# Atmega32AU-Basic.net
KiCad netlist of a schematic drawn in EAGLE
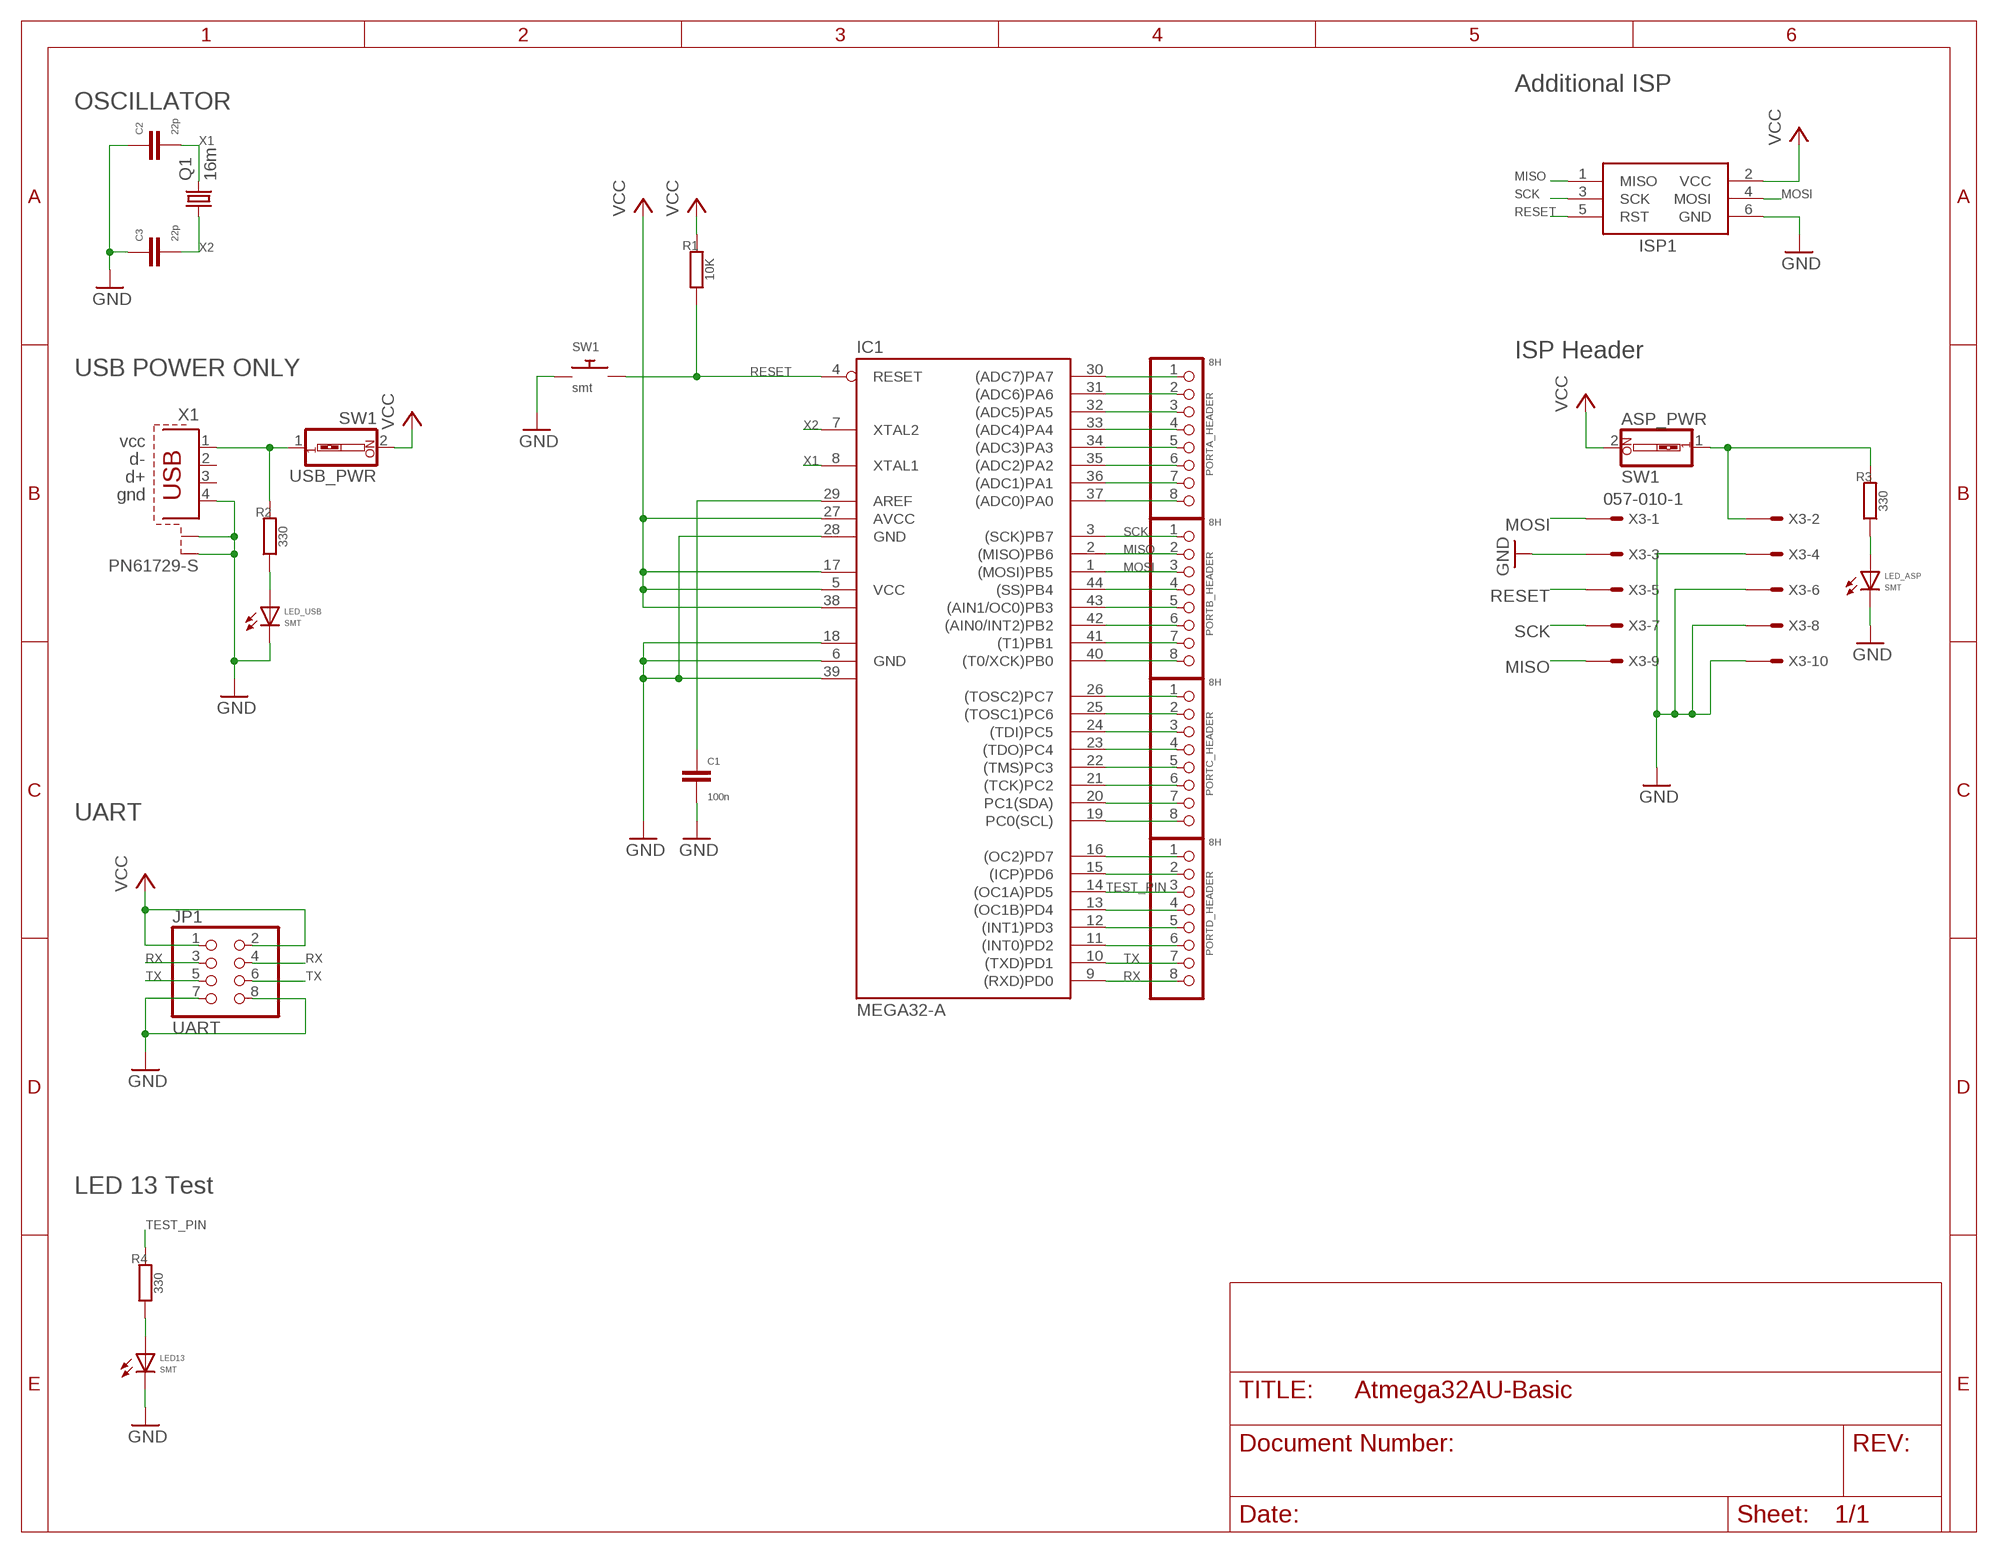
[diagram p0: schematic, sheet 1]

(export (version "E")
  (design (tool "Eeschema 10.0.6"))
  (components
    (comp (ref "ASP_PWR")
      (value "SW1")
      (footprint "eagle-import:EDG-01")
      (libsource (lib "eagle-import") (part "SW_DIP-1"))
    )
    (comp (ref "C1")
      (value "100n")
      (footprint "eagle-import:C1206")
      (libsource (lib "eagle-import") (part "C-EUC1206"))
    )
    (comp (ref "C2")
      (value "22p")
      (footprint "eagle-import:C1206")
      (libsource (lib "eagle-import") (part "C-EUC1206"))
    )
    (comp (ref "C3")
      (value "22p")
      (footprint "eagle-import:C1206")
      (libsource (lib "eagle-import") (part "C-EUC1206"))
    )
    (comp (ref "IC1")
      (value "MEGA32-A")
      (footprint "eagle-import:TQFP44")
      (fields (field (name "MPN") "ATMEGA32-16AU"))
      (libsource (lib "eagle-import") (part "MEGA32-A"))
    )
    (comp (ref "ISP1")
      (value "AVRISP-6")
      (footprint "eagle-import:AVRISP")
      (libsource (lib "eagle-import") (part "AVRISP-6"))
    )
    (comp (ref "JP1")
      (value "UART")
      (footprint "eagle-import:2X04")
      (libsource (lib "eagle-import") (part "PINHD-2X4"))
    )
    (comp (ref "LED13")
      (value "SMT")
      (footprint "eagle-import:1206")
      (libsource (lib "eagle-import") (part "LEDSMT1206"))
    )
    (comp (ref "LED_ASP")
      (value "SMT")
      (footprint "eagle-import:1206")
      (libsource (lib "eagle-import") (part "LEDSMT1206"))
    )
    (comp (ref "LED_USB")
      (value "SMT")
      (footprint "eagle-import:1206")
      (libsource (lib "eagle-import") (part "LEDSMT1206"))
    )
    (comp (ref "PORTA_HEADER")
      (value "8H")
      (footprint "eagle-import:1X08-BIG")
      (libsource (lib "eagle-import") (part "PINHD-1X8BIG"))
    )
    (comp (ref "PORTB_HEADER")
      (value "8H")
      (footprint "eagle-import:1X08-BIG")
      (libsource (lib "eagle-import") (part "PINHD-1X8BIG"))
    )
    (comp (ref "PORTC_HEADER")
      (value "8H")
      (footprint "eagle-import:1X08-BIG")
      (libsource (lib "eagle-import") (part "PINHD-1X8BIG"))
    )
    (comp (ref "PORTD_HEADER")
      (value "8H")
      (footprint "eagle-import:1X08-BIG")
      (libsource (lib "eagle-import") (part "PINHD-1X8BIG"))
    )
    (comp (ref "Q1")
      (value "16m")
      (footprint "eagle-import:HC49UP")
      (libsource (lib "eagle-import") (part "CRYSTALHC49UP"))
    )
    (comp (ref "R1")
      (value "10K")
      (footprint "eagle-import:M1206")
      (libsource (lib "eagle-import") (part "R-EU_M1206"))
    )
    (comp (ref "R2")
      (value "330")
      (footprint "eagle-import:M1206")
      (libsource (lib "eagle-import") (part "R-EU_M1206"))
    )
    (comp (ref "R3")
      (value "330")
      (footprint "eagle-import:M1206")
      (libsource (lib "eagle-import") (part "R-EU_M1206"))
    )
    (comp (ref "R4")
      (value "330")
      (footprint "eagle-import:M1206")
      (libsource (lib "eagle-import") (part "R-EU_M1206"))
    )
    (comp (ref "SW1")
      (value "smt")
      (footprint "eagle-import:TACT_PANA-EVQ")
      (libsource (lib "eagle-import") (part "SWITCH_PUSHBUTTONEVQ-PE"))
    )
    (comp (ref "USB_PWR")
      (value "SW1")
      (footprint "eagle-import:EDG-01")
      (libsource (lib "eagle-import") (part "SW_DIP-1"))
    )
    (comp (ref "X1")
      (value "PN61729-S")
      (footprint "eagle-import:PN61729-S")
      (libsource (lib "eagle-import") (part "PN61729-S"))
    )
    (comp (ref "X3")
      (value "057-010-1")
      (footprint "eagle-import:057-010-1")
      (libsource (lib "eagle-import") (part "057-010-1"))
    )
  )
  (nets
    (net (code "1") (name "/MISO") (class "Default")
      (node (ref "IC1") (pin "2") (pinfunction "(MISO)PB6_2") (pintype "bidirectional"))
      (node (ref "ISP1") (pin "1") (pinfunction "MISO_1") (pintype "input"))
      (node (ref "PORTB_HEADER") (pin "2") (pinfunction "2_2") (pintype "passive"))
      (node (ref "X3") (pin "9") (pinfunction "S_9") (pintype "passive"))
    )
    (net (code "2") (name "/MOSI") (class "Default")
      (node (ref "IC1") (pin "1") (pinfunction "(MOSI)PB5_1") (pintype "bidirectional"))
      (node (ref "ISP1") (pin "4") (pinfunction "MOSI_4") (pintype "output"))
      (node (ref "PORTB_HEADER") (pin "3") (pinfunction "3_3") (pintype "passive"))
      (node (ref "X3") (pin "1") (pinfunction "S_1") (pintype "passive"))
    )
    (net (code "3") (name "/RESET") (class "Default")
      (node (ref "IC1") (pin "4") (pinfunction "RESET_4") (pintype "input"))
      (node (ref "ISP1") (pin "5") (pinfunction "RST_5") (pintype "output"))
      (node (ref "R1") (pin "1") (pinfunction "1_1") (pintype "passive"))
      (node (ref "SW1") (pin "P$2") (pinfunction "P$2_P$2") (pintype "passive"))
      (node (ref "X3") (pin "5") (pinfunction "S_5") (pintype "passive"))
    )
    (net (code "4") (name "/RX") (class "Default")
      (node (ref "IC1") (pin "9") (pinfunction "(RXD)PD0_9") (pintype "bidirectional"))
      (node (ref "JP1") (pin "3") (pinfunction "3_3") (pintype "passive"))
      (node (ref "JP1") (pin "4") (pinfunction "4_4") (pintype "passive"))
      (node (ref "PORTD_HEADER") (pin "8") (pinfunction "8_8") (pintype "passive"))
    )
    (net (code "5") (name "/SCK") (class "Default")
      (node (ref "IC1") (pin "3") (pinfunction "(SCK)PB7_3") (pintype "bidirectional"))
      (node (ref "ISP1") (pin "3") (pinfunction "SCK_3") (pintype "output"))
      (node (ref "PORTB_HEADER") (pin "1") (pinfunction "1_1") (pintype "passive"))
      (node (ref "X3") (pin "7") (pinfunction "S_7") (pintype "passive"))
    )
    (net (code "6") (name "/TEST_PIN") (class "Default")
      (node (ref "IC1") (pin "14") (pinfunction "(OC1A)PD5_14") (pintype "bidirectional"))
      (node (ref "PORTD_HEADER") (pin "3") (pinfunction "3_3") (pintype "passive"))
      (node (ref "R4") (pin "2") (pinfunction "2_2") (pintype "passive"))
    )
    (net (code "7") (name "/TX") (class "Default")
      (node (ref "IC1") (pin "10") (pinfunction "(TXD)PD1_10") (pintype "bidirectional"))
      (node (ref "JP1") (pin "5") (pinfunction "5_5") (pintype "passive"))
      (node (ref "JP1") (pin "6") (pinfunction "6_6") (pintype "passive"))
      (node (ref "PORTD_HEADER") (pin "7") (pinfunction "7_7") (pintype "passive"))
    )
    (net (code "8") (name "/X1") (class "Default")
      (node (ref "C2") (pin "2") (pinfunction "2_2") (pintype "passive"))
      (node (ref "IC1") (pin "8") (pinfunction "XTAL1_8") (pintype "bidirectional"))
      (node (ref "Q1") (pin "2") (pinfunction "2_2") (pintype "passive"))
    )
    (net (code "9") (name "/X2") (class "Default")
      (node (ref "C3") (pin "2") (pinfunction "2_2") (pintype "passive"))
      (node (ref "IC1") (pin "7") (pinfunction "XTAL2_7") (pintype "bidirectional"))
      (node (ref "Q1") (pin "1") (pinfunction "1_1") (pintype "passive"))
    )
    (net (code "10") (name "GND") (class "Default")
      (node (ref "C1") (pin "2") (pinfunction "2_2") (pintype "passive"))
      (node (ref "C2") (pin "1") (pinfunction "1_1") (pintype "passive"))
      (node (ref "C3") (pin "1") (pinfunction "1_1") (pintype "passive"))
      (node (ref "IC1") (pin "18") (pinfunction "GND1_18") (pintype "power_in"))
      (node (ref "IC1") (pin "28") (pinfunction "GND_28") (pintype "power_in"))
      (node (ref "IC1") (pin "39") (pinfunction "GND2_39") (pintype "power_in"))
      (node (ref "IC1") (pin "6") (pinfunction "GND_6") (pintype "power_in"))
      (node (ref "ISP1") (pin "6") (pinfunction "GND_6") (pintype "power_in"))
      (node (ref "JP1") (pin "7") (pinfunction "7_7") (pintype "passive"))
      (node (ref "JP1") (pin "8") (pinfunction "8_8") (pintype "passive"))
      (node (ref "LED13") (pin "C") (pinfunction "C_C") (pintype "passive"))
      (node (ref "LED_ASP") (pin "C") (pinfunction "C_C") (pintype "passive"))
      (node (ref "LED_USB") (pin "C") (pinfunction "C_C") (pintype "passive"))
      (node (ref "SW1") (pin "P$1") (pinfunction "P$1_P$1") (pintype "passive"))
      (node (ref "X1") (pin "4") (pinfunction "4_4") (pintype "passive"))
      (node (ref "X1") (pin "S1") (pinfunction "S1_S1") (pintype "passive"))
      (node (ref "X1") (pin "S2") (pinfunction "S2_S2") (pintype "passive"))
      (node (ref "X3") (pin "10") (pinfunction "S_10") (pintype "passive"))
      (node (ref "X3") (pin "3") (pinfunction "S_3") (pintype "passive"))
      (node (ref "X3") (pin "4") (pinfunction "S_4") (pintype "passive"))
      (node (ref "X3") (pin "6") (pinfunction "S_6") (pintype "passive"))
      (node (ref "X3") (pin "8") (pinfunction "S_8") (pintype "passive"))
    )
    (net (code "11") (name "Net-(IC1-(ADC0)PA0)") (class "Default")
      (node (ref "IC1") (pin "37") (pinfunction "(ADC0)PA0_37") (pintype "bidirectional"))
      (node (ref "PORTA_HEADER") (pin "8") (pinfunction "8_8") (pintype "passive"))
    )
    (net (code "12") (name "Net-(IC1-(ADC1)PA1)") (class "Default")
      (node (ref "IC1") (pin "36") (pinfunction "(ADC1)PA1_36") (pintype "bidirectional"))
      (node (ref "PORTA_HEADER") (pin "7") (pinfunction "7_7") (pintype "passive"))
    )
    (net (code "13") (name "Net-(IC1-(ADC2)PA2)") (class "Default")
      (node (ref "IC1") (pin "35") (pinfunction "(ADC2)PA2_35") (pintype "bidirectional"))
      (node (ref "PORTA_HEADER") (pin "6") (pinfunction "6_6") (pintype "passive"))
    )
    (net (code "14") (name "Net-(IC1-(ADC3)PA3)") (class "Default")
      (node (ref "IC1") (pin "34") (pinfunction "(ADC3)PA3_34") (pintype "bidirectional"))
      (node (ref "PORTA_HEADER") (pin "5") (pinfunction "5_5") (pintype "passive"))
    )
    (net (code "15") (name "Net-(IC1-(ADC4)PA4)") (class "Default")
      (node (ref "IC1") (pin "33") (pinfunction "(ADC4)PA4_33") (pintype "bidirectional"))
      (node (ref "PORTA_HEADER") (pin "4") (pinfunction "4_4") (pintype "passive"))
    )
    (net (code "16") (name "Net-(IC1-(ADC5)PA5)") (class "Default")
      (node (ref "IC1") (pin "32") (pinfunction "(ADC5)PA5_32") (pintype "bidirectional"))
      (node (ref "PORTA_HEADER") (pin "3") (pinfunction "3_3") (pintype "passive"))
    )
    (net (code "17") (name "Net-(IC1-(ADC6)PA6)") (class "Default")
      (node (ref "IC1") (pin "31") (pinfunction "(ADC6)PA6_31") (pintype "bidirectional"))
      (node (ref "PORTA_HEADER") (pin "2") (pinfunction "2_2") (pintype "passive"))
    )
    (net (code "18") (name "Net-(IC1-(ADC7)PA7)") (class "Default")
      (node (ref "IC1") (pin "30") (pinfunction "(ADC7)PA7_30") (pintype "bidirectional"))
      (node (ref "PORTA_HEADER") (pin "1") (pinfunction "1_1") (pintype "passive"))
    )
    (net (code "19") (name "Net-(IC1-(AIN0{slash}INT2)PB2)") (class "Default")
      (node (ref "IC1") (pin "42") (pinfunction "(AIN0/INT2)PB2_42") (pintype "bidirectional"))
      (node (ref "PORTB_HEADER") (pin "6") (pinfunction "6_6") (pintype "passive"))
    )
    (net (code "20") (name "Net-(IC1-(AIN1{slash}OC0)PB3)") (class "Default")
      (node (ref "IC1") (pin "43") (pinfunction "(AIN1/OC0)PB3_43") (pintype "bidirectional"))
      (node (ref "PORTB_HEADER") (pin "5") (pinfunction "5_5") (pintype "passive"))
    )
    (net (code "21") (name "Net-(IC1-(ICP)PD6)") (class "Default")
      (node (ref "IC1") (pin "15") (pinfunction "(ICP)PD6_15") (pintype "bidirectional"))
      (node (ref "PORTD_HEADER") (pin "2") (pinfunction "2_2") (pintype "passive"))
    )
    (net (code "22") (name "Net-(IC1-(INT0)PD2)") (class "Default")
      (node (ref "IC1") (pin "11") (pinfunction "(INT0)PD2_11") (pintype "bidirectional"))
      (node (ref "PORTD_HEADER") (pin "6") (pinfunction "6_6") (pintype "passive"))
    )
    (net (code "23") (name "Net-(IC1-(INT1)PD3)") (class "Default")
      (node (ref "IC1") (pin "12") (pinfunction "(INT1)PD3_12") (pintype "bidirectional"))
      (node (ref "PORTD_HEADER") (pin "5") (pinfunction "5_5") (pintype "passive"))
    )
    (net (code "24") (name "Net-(IC1-(OC1B)PD4)") (class "Default")
      (node (ref "IC1") (pin "13") (pinfunction "(OC1B)PD4_13") (pintype "bidirectional"))
      (node (ref "PORTD_HEADER") (pin "4") (pinfunction "4_4") (pintype "passive"))
    )
    (net (code "25") (name "Net-(IC1-(OC2)PD7)") (class "Default")
      (node (ref "IC1") (pin "16") (pinfunction "(OC2)PD7_16") (pintype "bidirectional"))
      (node (ref "PORTD_HEADER") (pin "1") (pinfunction "1_1") (pintype "passive"))
    )
    (net (code "26") (name "Net-(IC1-(SS)PB4)") (class "Default")
      (node (ref "IC1") (pin "44") (pinfunction "(SS)PB4_44") (pintype "bidirectional"))
      (node (ref "PORTB_HEADER") (pin "4") (pinfunction "4_4") (pintype "passive"))
    )
    (net (code "27") (name "Net-(IC1-(T0{slash}XCK)PB0)") (class "Default")
      (node (ref "IC1") (pin "40") (pinfunction "(T0/XCK)PB0_40") (pintype "bidirectional"))
      (node (ref "PORTB_HEADER") (pin "8") (pinfunction "8_8") (pintype "passive"))
    )
    (net (code "28") (name "Net-(IC1-(T1)PB1)") (class "Default")
      (node (ref "IC1") (pin "41") (pinfunction "(T1)PB1_41") (pintype "bidirectional"))
      (node (ref "PORTB_HEADER") (pin "7") (pinfunction "7_7") (pintype "passive"))
    )
    (net (code "29") (name "Net-(IC1-(TCK)PC2)") (class "Default")
      (node (ref "IC1") (pin "21") (pinfunction "(TCK)PC2_21") (pintype "bidirectional"))
      (node (ref "PORTC_HEADER") (pin "6") (pinfunction "6_6") (pintype "passive"))
    )
    (net (code "30") (name "Net-(IC1-(TDI)PC5)") (class "Default")
      (node (ref "IC1") (pin "24") (pinfunction "(TDI)PC5_24") (pintype "bidirectional"))
      (node (ref "PORTC_HEADER") (pin "3") (pinfunction "3_3") (pintype "passive"))
    )
    (net (code "31") (name "Net-(IC1-(TDO)PC4)") (class "Default")
      (node (ref "IC1") (pin "23") (pinfunction "(TDO)PC4_23") (pintype "bidirectional"))
      (node (ref "PORTC_HEADER") (pin "4") (pinfunction "4_4") (pintype "passive"))
    )
    (net (code "32") (name "Net-(IC1-(TMS)PC3)") (class "Default")
      (node (ref "IC1") (pin "22") (pinfunction "(TMS)PC3_22") (pintype "bidirectional"))
      (node (ref "PORTC_HEADER") (pin "5") (pinfunction "5_5") (pintype "passive"))
    )
    (net (code "33") (name "Net-(IC1-(TOSC1)PC6)") (class "Default")
      (node (ref "IC1") (pin "25") (pinfunction "(TOSC1)PC6_25") (pintype "bidirectional"))
      (node (ref "PORTC_HEADER") (pin "2") (pinfunction "2_2") (pintype "passive"))
    )
    (net (code "34") (name "Net-(IC1-(TOSC2)PC7)") (class "Default")
      (node (ref "IC1") (pin "26") (pinfunction "(TOSC2)PC7_26") (pintype "bidirectional"))
      (node (ref "PORTC_HEADER") (pin "1") (pinfunction "1_1") (pintype "passive"))
    )
    (net (code "35") (name "Net-(IC1-AREF)") (class "Default")
      (node (ref "C1") (pin "1") (pinfunction "1_1") (pintype "passive"))
      (node (ref "IC1") (pin "29") (pinfunction "AREF_29") (pintype "passive"))
    )
    (net (code "36") (name "Net-(IC1-PC0(SCL))") (class "Default")
      (node (ref "IC1") (pin "19") (pinfunction "PC0(SCL)_19") (pintype "bidirectional"))
      (node (ref "PORTC_HEADER") (pin "8") (pinfunction "8_8") (pintype "passive"))
    )
    (net (code "37") (name "Net-(IC1-PC1(SDA))") (class "Default")
      (node (ref "IC1") (pin "20") (pinfunction "PC1(SDA)_20") (pintype "bidirectional"))
      (node (ref "PORTC_HEADER") (pin "7") (pinfunction "7_7") (pintype "passive"))
    )
    (net (code "38") (name "Net-(LED13-PadA)") (class "Default")
      (node (ref "LED13") (pin "A") (pinfunction "A_A") (pintype "passive"))
      (node (ref "R4") (pin "1") (pinfunction "1_1") (pintype "passive"))
    )
    (net (code "39") (name "Net-(LED_ASP-PadA)") (class "Default")
      (node (ref "LED_ASP") (pin "A") (pinfunction "A_A") (pintype "passive"))
      (node (ref "R3") (pin "1") (pinfunction "1_1") (pintype "passive"))
    )
    (net (code "40") (name "Net-(LED_USB-PadA)") (class "Default")
      (node (ref "LED_USB") (pin "A") (pinfunction "A_A") (pintype "passive"))
      (node (ref "R2") (pin "1") (pinfunction "1_1") (pintype "passive"))
    )
    (net (code "41") (name "Net-(R2-Pad2)") (class "Default")
      (node (ref "R2") (pin "2") (pinfunction "2_2") (pintype "passive"))
      (node (ref "USB_PWR") (pin "1") (pinfunction "1_1") (pintype "passive"))
      (node (ref "X1") (pin "1") (pinfunction "1_1") (pintype "passive"))
    )
    (net (code "42") (name "Net-(X3C-S)") (class "Default")
      (node (ref "ASP_PWR") (pin "1") (pinfunction "1_1") (pintype "passive"))
      (node (ref "R3") (pin "2") (pinfunction "2_2") (pintype "passive"))
      (node (ref "X3") (pin "2") (pinfunction "S_2") (pintype "passive"))
    )
    (net (code "43") (name "VCC") (class "Default")
      (node (ref "ASP_PWR") (pin "2") (pinfunction "2_2") (pintype "passive"))
      (node (ref "IC1") (pin "17") (pinfunction "VCC1_17") (pintype "power_in"))
      (node (ref "IC1") (pin "27") (pinfunction "AVCC_27") (pintype "power_in"))
      (node (ref "IC1") (pin "38") (pinfunction "VCC2_38") (pintype "power_in"))
      (node (ref "IC1") (pin "5") (pinfunction "VCC_5") (pintype "power_in"))
      (node (ref "ISP1") (pin "2") (pinfunction "VCC_2") (pintype "power_in"))
      (node (ref "JP1") (pin "1") (pinfunction "1_1") (pintype "passive"))
      (node (ref "JP1") (pin "2") (pinfunction "2_2") (pintype "passive"))
      (node (ref "R1") (pin "2") (pinfunction "2_2") (pintype "passive"))
      (node (ref "USB_PWR") (pin "2") (pinfunction "2_2") (pintype "passive"))
    )
    (net (code "44") (name "unconnected-(X1-Pad2)") (class "Default")
      (node (ref "X1") (pin "2") (pinfunction "2_2") (pintype "passive"))
    )
    (net (code "45") (name "unconnected-(X1-Pad3)") (class "Default")
      (node (ref "X1") (pin "3") (pinfunction "3_3") (pintype "passive"))
    )
  )
)
